# IO.net
KiCad netlist of a schematic drawn in Altium Designer
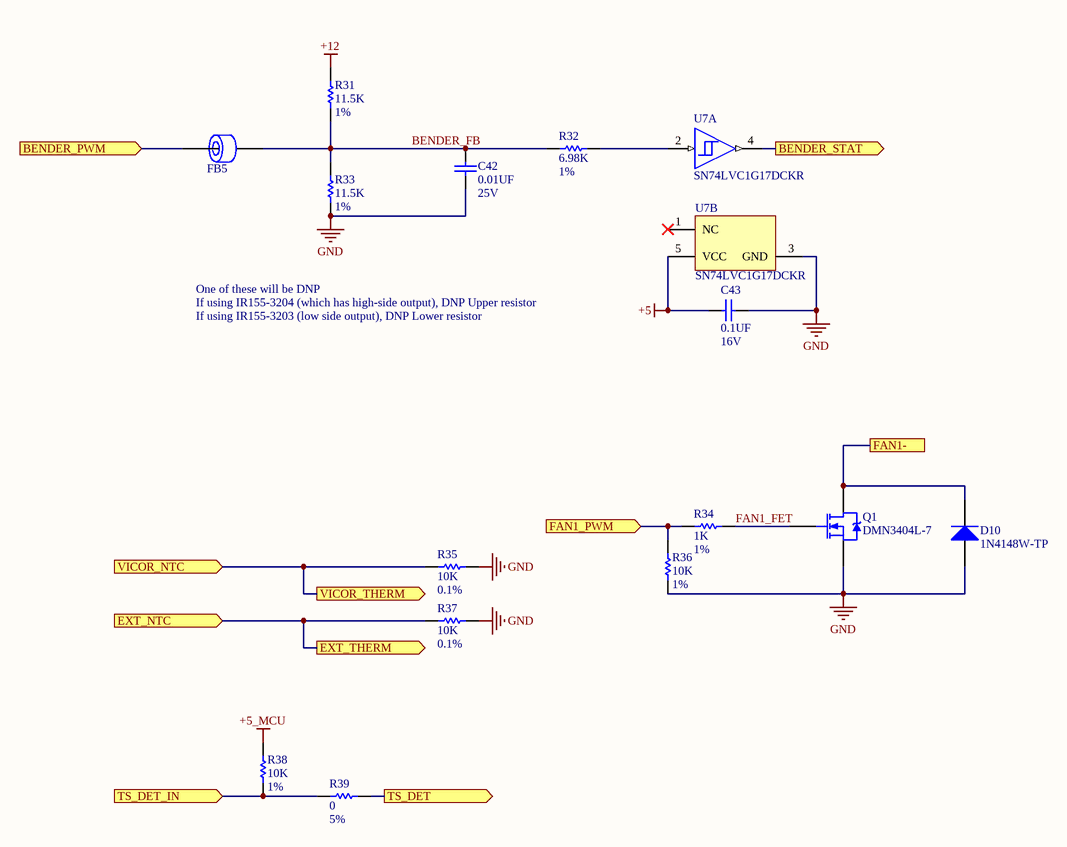
[diagram p0: IO.SchDoc]

(export (version "E")
  (design (tool "Eeschema 10.0.6"))
  (components
    (comp (ref "C42")
      (value "CAP 0603 0.01UF 25V 10% X7R")
      (footprint "0603_CAP")
      (description "Capacitor Surface Mount 0603 Footprint 0.01UF 25V 10% Tolerance Ceramic X7R")
      (fields
        (field (name "VAL") "0.01UF")
        (field (name "VOL") "25V")
        (field (name "MANUFACTURER") "Various")
        (field (name "VOLTAGE") "25V")
      )
      (libsource (lib "Passive Components") (part "cap"))
    )
    (comp (ref "C43")
      (value "CAP 0603 0.1UF 16V 10% X7R")
      (footprint "0603_CAP")
      (description "Capacitor Surface Mount 0603 Footprint 0.1UF 16V 10% Tolerance Ceramic X7R")
      (fields
        (field (name "VAL") "0.1UF")
        (field (name "VOL") "16V")
        (field (name "MANUFACTURER") "Various")
        (field (name "VOLTAGE") "16V")
      )
      (libsource (lib "Passive Components") (part "cap"))
    )
    (comp (ref "D10")
      (value "1N4148W-TP")
      (footprint "MCC-SOD123_V")
      (description "High Speed Switching Diode, 400 mW, 150 mA, -65 to 150 degC, 2-Pin SOD123, RoHS, Tape and Reel")
      (fields (field (name "MANUFACTURER") "Micro Commercial Components"))
      (libsource (lib "Altium Content Vault") (part "D-AK-2"))
    )
    (comp (ref "FB5")
      (value "Ferrite Chip 2500 Ohms")
      (footprint "0603")
      (description "Ferrite Chip 200 mA 2500 Ohms Differential Mode - Single 0603 Footprint")
      (fields (field (name "MANUFACTURER") "TDK"))
      (libsource (lib "Passive Components") (part "Ferrite Bead"))
    )
    (comp (ref "Q1")
      (value "DMN3404L-7")
      (footprint "SOT23-FET-DI")
      (description "N-Channel 30V 5.8A (Ta) 720mW (Ta) Surface Mount SOT-23-3")
      (fields (field (name "MANUFACTURER") "Diodes"))
      (libsource (lib "AERO Parts") (part "DMN3404L-7"))
    )
    (comp (ref "R31")
      (value "RES 0603 11.5K 1%")
      (footprint "0603_RES")
      (description "Resistor Surface Mount, 11.5K Ohms, 0603 Footprint, 1% Tolerance 0.1W")
      (fields
        (field (name "VAL") "11.5K")
        (field (name "TOL") "1%")
        (field (name "MANUFACTURER") "Various")
        (field (name "TOLERANCE") "1%")
      )
      (libsource (lib "Passive Components") (part "res"))
    )
    (comp (ref "R32")
      (value "RES 0603 6.98K 1%")
      (footprint "0603_RES")
      (description "Resistor Surface Mount, 6.98K Ohms, 0603 Footprint, 1% Tolerance 0.1W")
      (fields
        (field (name "VAL") "6.98K")
        (field (name "TOL") "1%")
        (field (name "MANUFACTURER") "Various")
        (field (name "TOLERANCE") "1%")
      )
      (libsource (lib "Passive Components") (part "res"))
    )
    (comp (ref "R33")
      (value "RES 0603 11.5K 1%")
      (footprint "0603_RES")
      (description "Resistor Surface Mount, 11.5K Ohms, 0603 Footprint, 1% Tolerance 0.1W")
      (fields
        (field (name "VAL") "11.5K")
        (field (name "TOL") "1%")
        (field (name "MANUFACTURER") "Various")
        (field (name "TOLERANCE") "1%")
      )
      (libsource (lib "Passive Components") (part "res"))
    )
    (comp (ref "R34")
      (value "RES 0603 1K 1%")
      (footprint "0603_RES")
      (description "Resistor Surface Mount, 1K Ohms, 0603 Footprint, 1% Tolerance 0.1W")
      (fields
        (field (name "VAL") "1K")
        (field (name "TOL") "1%")
        (field (name "MANUFACTURER") "Various")
        (field (name "TOLERANCE") "1%")
      )
      (libsource (lib "Passive Components") (part "res"))
    )
    (comp (ref "R35")
      (value "RES 0603 10K 0.1%")
      (footprint "0603_RES")
      (description "Resistor Surface Mount, 10K Ohms, 0603 Footprint, 0.1% Tolerance 0.1W")
      (fields
        (field (name "VAL") "10K")
        (field (name "TOL") "0.1%")
        (field (name "MANUFACTURER") "Various")
        (field (name "TOLERANCE") "0.1%")
      )
      (libsource (lib "Passive Components") (part "res"))
    )
    (comp (ref "R36")
      (value "RES 0603 10K 1%")
      (footprint "0603_RES")
      (description "Resistor Surface Mount, 10K Ohms, 0603 Footprint, 1% Tolerance 0.1W")
      (fields
        (field (name "VAL") "10K")
        (field (name "TOL") "1%")
        (field (name "MANUFACTURER") "Various")
        (field (name "TOLERANCE") "1%")
      )
      (libsource (lib "Passive Components") (part "res"))
    )
    (comp (ref "R37")
      (value "RES 0603 10K 0.1%")
      (footprint "0603_RES")
      (description "Resistor Surface Mount, 10K Ohms, 0603 Footprint, 0.1% Tolerance 0.1W")
      (fields
        (field (name "VAL") "10K")
        (field (name "TOL") "0.1%")
        (field (name "MANUFACTURER") "Various")
        (field (name "TOLERANCE") "0.1%")
      )
      (libsource (lib "Passive Components") (part "res"))
    )
    (comp (ref "R38")
      (value "RES 0603 10K 1%")
      (footprint "0603_RES")
      (description "Resistor Surface Mount, 10K Ohms, 0603 Footprint, 1% Tolerance 0.1W")
      (fields
        (field (name "VAL") "10K")
        (field (name "TOL") "1%")
        (field (name "MANUFACTURER") "Various")
        (field (name "TOLERANCE") "1%")
      )
      (libsource (lib "Passive Components") (part "res"))
    )
    (comp (ref "R39")
      (value "RES 0603 0 5%")
      (footprint "0603_RES")
      (description "Resistor Surface Mount, 0 Ohms, 0603 Footprint, 5% Tolerance 0.1W")
      (fields
        (field (name "VAL") "0")
        (field (name "TOL") "5%")
        (field (name "MANUFACTURER") "Various")
        (field (name "TOLERANCE") "5%")
      )
      (libsource (lib "Passive Components") (part "res"))
    )
    (comp (ref "U7")
      (value "SN74LVC1G17DCKR")
      (footprint "DCK0005A_L")
      (description "Single Schmitt-Trigger Buffer, DCK0005A, LARGE T&R")
      (fields
        (field (name "MANUFACTURER") "Texas Instruments")
        (field (name "GENERIC PART NUMBER") "SN74LVC1G17")
      )
      (libsource (lib "Altium Content Vault") (part "TI-SN74XXX1XXX-XX-5-SCHMITT"))
    )
  )
  (nets
    (net (code "1") (name "+5") (class "Default")
      (node (ref "C43") (pin "1") (pinfunction "1_1") (pintype "passive"))
      (node (ref "U7") (pin "5") (pinfunction "VCC_5") (pintype "power_in"))
    )
    (net (code "2") (name "+5_MCU") (class "Default")
      (node (ref "R38") (pin "2") (pinfunction "2_2") (pintype "passive"))
    )
    (net (code "3") (name "+12") (class "Default")
      (node (ref "R31") (pin "2") (pinfunction "2_2") (pintype "passive"))
    )
    (net (code "4") (name "/BENDER_FB") (class "Default")
      (node (ref "C42") (pin "2") (pinfunction "2_2") (pintype "passive"))
      (node (ref "FB5") (pin "2") (pinfunction "2_2") (pintype "passive"))
      (node (ref "R31") (pin "1") (pinfunction "1_1") (pintype "passive"))
      (node (ref "R32") (pin "2") (pinfunction "2_2") (pintype "passive"))
      (node (ref "R33") (pin "2") (pinfunction "2_2") (pintype "passive"))
    )
    (net (code "5") (name "/BENDER_PWM") (class "Default")
      (node (ref "FB5") (pin "1") (pinfunction "1_1") (pintype "passive"))
    )
    (net (code "6") (name "/BENDER_STAT") (class "Default")
      (node (ref "U7") (pin "4") (pinfunction "Y_4") (pintype "output"))
    )
    (net (code "7") (name "/EXT_NTC") (class "Default")
      (node (ref "R37") (pin "1") (pinfunction "1_1") (pintype "passive"))
    )
    (net (code "8") (name "/FAN1-") (class "Default")
      (node (ref "D10") (pin "2") (pinfunction "K_2") (pintype "passive"))
      (node (ref "Q1") (pin "3") (pinfunction "D_3") (pintype "passive"))
    )
    (net (code "9") (name "/FAN1_FET") (class "Default")
      (node (ref "Q1") (pin "1") (pinfunction "G_1") (pintype "passive"))
      (node (ref "R34") (pin "2") (pinfunction "2_2") (pintype "passive"))
    )
    (net (code "10") (name "/FAN1_PWM") (class "Default")
      (node (ref "R34") (pin "1") (pinfunction "1_1") (pintype "passive"))
      (node (ref "R36") (pin "2") (pinfunction "2_2") (pintype "passive"))
    )
    (net (code "11") (name "/TS_DET") (class "Default")
      (node (ref "R39") (pin "2") (pinfunction "2_2") (pintype "passive"))
    )
    (net (code "12") (name "/TS_DET_IN") (class "Default")
      (node (ref "R38") (pin "1") (pinfunction "1_1") (pintype "passive"))
      (node (ref "R39") (pin "1") (pinfunction "1_1") (pintype "passive"))
    )
    (net (code "13") (name "/VICOR_NTC") (class "Default")
      (node (ref "R35") (pin "1") (pinfunction "1_1") (pintype "passive"))
    )
    (net (code "14") (name "GND") (class "Default")
      (node (ref "C42") (pin "1") (pinfunction "1_1") (pintype "passive"))
      (node (ref "C43") (pin "2") (pinfunction "2_2") (pintype "passive"))
      (node (ref "D10") (pin "1") (pinfunction "A_1") (pintype "passive"))
      (node (ref "Q1") (pin "2") (pinfunction "S_2") (pintype "passive"))
      (node (ref "R33") (pin "1") (pinfunction "1_1") (pintype "passive"))
      (node (ref "R35") (pin "2") (pinfunction "2_2") (pintype "passive"))
      (node (ref "R36") (pin "1") (pinfunction "1_1") (pintype "passive"))
      (node (ref "R37") (pin "2") (pinfunction "2_2") (pintype "passive"))
      (node (ref "U7") (pin "3") (pinfunction "GND_3") (pintype "power_in"))
    )
    (net (code "15") (name "Net-(U7A-A)") (class "Default")
      (node (ref "R32") (pin "1") (pinfunction "1_1") (pintype "passive"))
      (node (ref "U7") (pin "2") (pinfunction "A_2") (pintype "input"))
    )
    (net (code "16") (name "unconnected-(U7B-NC-Pad1)") (class "Default")
      (node (ref "U7") (pin "1") (pinfunction "NC_1") (pintype "passive+no_connect"))
    )
  )
)
